# RF.net
KiCad netlist of a schematic drawn in Altium Designer
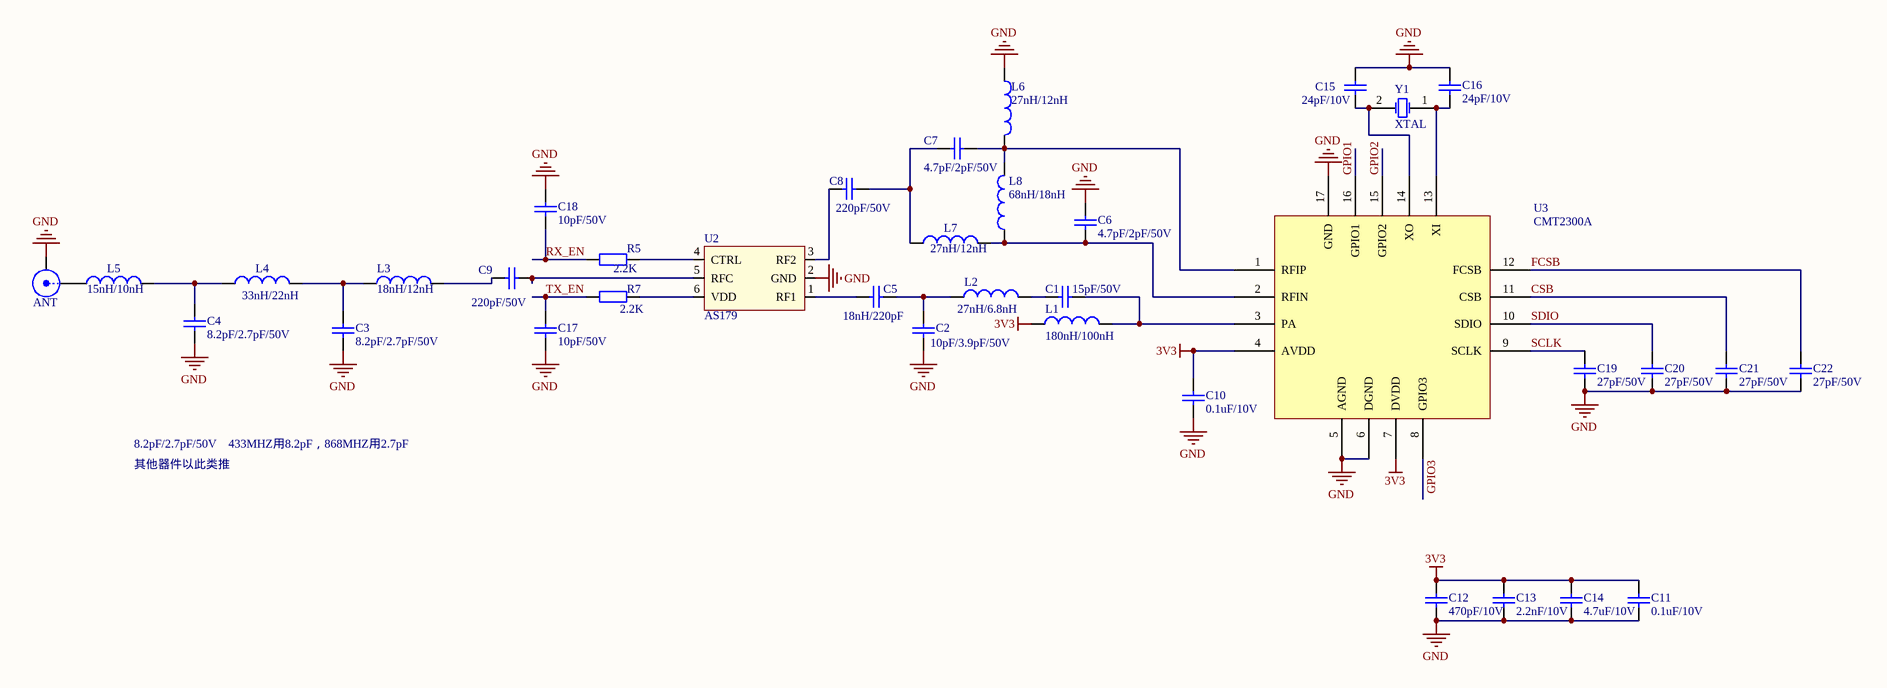
[diagram p0: RF.SchDoc]

(export (version "E")
  (design (tool "Eeschema 10.0.6"))
  (components
    (comp (ref "ANT")
      (value "~")
      (footprint "SMA Straight SMD")
      (description "SMA Straight Connector")
      (fields (field (name "PUBLISHER") "Altium Limited"))
      (libsource (lib "SX1276_e266v02a") (part "SMA"))
    )
    (comp (ref "C1")
      (value "15pF/50V")
      (footprint "0603C")
      (description "Capacitor")
      (fields (field (name "PUBLISHER") "Altium Limited"))
      (libsource (lib "Miscellaneous Devices") (part "Cap"))
    )
    (comp (ref "C2")
      (value "10pF/3.9pF/50V")
      (footprint "0603C")
      (description "Capacitor")
      (fields (field (name "PUBLISHER") "Altium Limited"))
      (libsource (lib "Miscellaneous Devices") (part "Cap"))
    )
    (comp (ref "C3")
      (value "8.2pF/2.7pF/50V")
      (footprint "0603C")
      (description "Capacitor")
      (fields (field (name "PUBLISHER") "Altium Limited"))
      (libsource (lib "Miscellaneous Devices") (part "Cap"))
    )
    (comp (ref "C4")
      (value "8.2pF/2.7pF/50V")
      (footprint "0603C")
      (description "Capacitor")
      (fields (field (name "PUBLISHER") "Altium Limited"))
      (libsource (lib "Miscellaneous Devices") (part "Cap"))
    )
    (comp (ref "C5")
      (value "18nH/220pF")
      (footprint "0603C")
      (description "Capacitor")
      (fields (field (name "PUBLISHER") "Altium Limited"))
      (libsource (lib "Miscellaneous Devices") (part "Cap"))
    )
    (comp (ref "C6")
      (value "4.7pF/2pF/50V")
      (footprint "0603C")
      (description "Capacitor")
      (fields (field (name "PUBLISHER") "Altium Limited"))
      (libsource (lib "Miscellaneous Devices") (part "Cap"))
    )
    (comp (ref "C7")
      (value "4.7pF/2pF/50V")
      (footprint "0603C")
      (description "Capacitor")
      (fields (field (name "PUBLISHER") "Altium Limited"))
      (libsource (lib "Miscellaneous Devices") (part "Cap"))
    )
    (comp (ref "C8")
      (value "220pF/50V")
      (footprint "0603C")
      (description "Capacitor")
      (fields (field (name "PUBLISHER") "Altium Limited"))
      (libsource (lib "Miscellaneous Devices") (part "Cap"))
    )
    (comp (ref "C9")
      (value "220pF/50V")
      (footprint "0603C")
      (description "Capacitor")
      (fields (field (name "PUBLISHER") "Altium Limited"))
      (libsource (lib "Miscellaneous Devices") (part "Cap"))
    )
    (comp (ref "C10")
      (value "0.1uF/10V")
      (footprint "0603C")
      (description "Capacitor")
      (fields (field (name "PUBLISHER") "Altium Limited"))
      (libsource (lib "Miscellaneous Devices") (part "Cap"))
    )
    (comp (ref "C11")
      (value "0.1uF/10V")
      (footprint "0603C")
      (description "Capacitor")
      (fields (field (name "PUBLISHER") "Altium Limited"))
      (libsource (lib "Miscellaneous Devices") (part "Cap"))
    )
    (comp (ref "C12")
      (value "470pF/10V")
      (footprint "0603C")
      (description "Capacitor")
      (fields (field (name "PUBLISHER") "Altium Limited"))
      (libsource (lib "Miscellaneous Devices") (part "Cap"))
    )
    (comp (ref "C13")
      (value "2.2nF/10V")
      (footprint "0603C")
      (description "Capacitor")
      (fields (field (name "PUBLISHER") "Altium Limited"))
      (libsource (lib "Miscellaneous Devices") (part "Cap"))
    )
    (comp (ref "C14")
      (value "4.7uF/10V")
      (footprint "0603C")
      (description "Capacitor")
      (fields (field (name "PUBLISHER") "Altium Limited"))
      (libsource (lib "Miscellaneous Devices") (part "Cap"))
    )
    (comp (ref "C15")
      (value "24pF/10V")
      (footprint "0603C")
      (description "Capacitor")
      (fields (field (name "PUBLISHER") "Altium Limited"))
      (libsource (lib "Miscellaneous Devices") (part "Cap"))
    )
    (comp (ref "C16")
      (value "24pF/10V")
      (footprint "0603C")
      (description "Capacitor")
      (fields (field (name "PUBLISHER") "Altium Limited"))
      (libsource (lib "Miscellaneous Devices") (part "Cap"))
    )
    (comp (ref "C17")
      (value "10pF/50V")
      (footprint "0603C")
      (description "Capacitor")
      (fields (field (name "PUBLISHER") "Altium Limited"))
      (libsource (lib "Miscellaneous Devices") (part "Cap"))
    )
    (comp (ref "C18")
      (value "10pF/50V")
      (footprint "0603C")
      (description "Capacitor")
      (fields (field (name "PUBLISHER") "Altium Limited"))
      (libsource (lib "Miscellaneous Devices") (part "Cap"))
    )
    (comp (ref "C19")
      (value "27pF/50V")
      (footprint "0603C")
      (description "Capacitor")
      (fields (field (name "PUBLISHER") "Altium Limited"))
      (libsource (lib "Miscellaneous Devices") (part "Cap"))
    )
    (comp (ref "C20")
      (value "27pF/50V")
      (footprint "0603C")
      (description "Capacitor")
      (fields (field (name "PUBLISHER") "Altium Limited"))
      (libsource (lib "Miscellaneous Devices") (part "Cap"))
    )
    (comp (ref "C21")
      (value "27pF/50V")
      (footprint "0603C")
      (description "Capacitor")
      (fields (field (name "PUBLISHER") "Altium Limited"))
      (libsource (lib "Miscellaneous Devices") (part "Cap"))
    )
    (comp (ref "C22")
      (value "27pF/50V")
      (footprint "0603C")
      (description "Capacitor")
      (fields (field (name "PUBLISHER") "Altium Limited"))
      (libsource (lib "Miscellaneous Devices") (part "Cap"))
    )
    (comp (ref "L1")
      (value "180nH/100nH")
      (footprint "0603R")
      (description "Inductor")
      (fields (field (name "PUBLISHER") "Altium Limited"))
      (libsource (lib "Miscellaneous Devices") (part "Inductor"))
    )
    (comp (ref "L2")
      (value "27nH/6.8nH")
      (footprint "0603R")
      (description "Inductor")
      (fields (field (name "PUBLISHER") "Altium Limited"))
      (libsource (lib "Miscellaneous Devices") (part "Inductor"))
    )
    (comp (ref "L3")
      (value "18nH/12nH")
      (footprint "0603R")
      (description "Inductor")
      (fields (field (name "PUBLISHER") "Altium Limited"))
      (libsource (lib "Miscellaneous Devices") (part "Inductor"))
    )
    (comp (ref "L4")
      (value "33nH/22nH")
      (footprint "0603R")
      (description "Inductor")
      (fields (field (name "PUBLISHER") "Altium Limited"))
      (libsource (lib "Miscellaneous Devices") (part "Inductor"))
    )
    (comp (ref "L5")
      (value "15nH/10nH")
      (footprint "0603R")
      (description "Inductor")
      (fields (field (name "PUBLISHER") "Altium Limited"))
      (libsource (lib "Miscellaneous Devices") (part "Inductor"))
    )
    (comp (ref "L6")
      (value "27nH/12nH")
      (footprint "0603R")
      (description "Inductor")
      (fields (field (name "PUBLISHER") "Altium Limited"))
      (libsource (lib "Miscellaneous Devices") (part "Inductor"))
    )
    (comp (ref "L7")
      (value "27nH/12nH")
      (footprint "0603R")
      (description "Inductor")
      (fields (field (name "PUBLISHER") "Altium Limited"))
      (libsource (lib "Miscellaneous Devices") (part "Inductor"))
    )
    (comp (ref "L8")
      (value "68nH/18nH")
      (footprint "0603R")
      (description "Inductor")
      (fields (field (name "PUBLISHER") "Altium Limited"))
      (libsource (lib "Miscellaneous Devices") (part "Inductor"))
    )
    (comp (ref "R5")
      (value "2.2K")
      (footprint "0603R")
      (description "Resistor")
      (fields (field (name "PUBLISHER") "Altium Limited"))
      (libsource (lib "Miscellaneous Devices") (part "Res2"))
    )
    (comp (ref "R7")
      (value "2.2K")
      (footprint "0603R")
      (description "Resistor")
      (fields (field (name "PUBLISHER") "Altium Limited"))
      (libsource (lib "Miscellaneous Devices") (part "Res2"))
    )
    (comp (ref "U2")
      (value "AS179")
      (description "PE4259 Peregrine RF Switch")
      (libsource (lib "SX1276_e266v02a") (part "PE4259 RF Switch"))
    )
    (comp (ref "U3") (value "CMT2300A") (libsource (lib "Schlib_20110825") (part "CMT2300A")))
    (comp (ref "Y1")
      (value "XTAL")
      (footprint "BCY-W2/D3.1")
      (description "Crystal Oscillator")
      (fields (field (name "PUBLISHER") "Altium Limited"))
      (libsource (lib "Miscellaneous Devices") (part "XTAL"))
    )
  )
  (nets
    (net (code "1") (name "/CSB") (class "Default")
      (node (ref "C21") (pin "1") (pinfunction "1_1") (pintype "passive"))
      (node (ref "U3") (pin "11") (pinfunction "CSB_11") (pintype "passive"))
    )
    (net (code "2") (name "/FCSB") (class "Default")
      (node (ref "C22") (pin "1") (pinfunction "1_1") (pintype "passive"))
      (node (ref "U3") (pin "12") (pinfunction "FCSB_12") (pintype "passive"))
    )
    (net (code "3") (name "/GPIO1") (class "Default")
      (node (ref "U3") (pin "16") (pinfunction "GPIO1_16") (pintype "passive"))
    )
    (net (code "4") (name "/GPIO2") (class "Default")
      (node (ref "U3") (pin "15") (pinfunction "GPIO2_15") (pintype "passive"))
    )
    (net (code "5") (name "/GPIO3") (class "Default")
      (node (ref "U3") (pin "8") (pinfunction "GPIO3_8") (pintype "passive"))
    )
    (net (code "6") (name "/RX_EN") (class "Default")
      (node (ref "C18") (pin "1") (pinfunction "1_1") (pintype "passive"))
      (node (ref "R5") (pin "2") (pinfunction "2_2") (pintype "passive"))
    )
    (net (code "7") (name "/SCLK") (class "Default")
      (node (ref "C19") (pin "1") (pinfunction "1_1") (pintype "passive"))
      (node (ref "U3") (pin "9") (pinfunction "SCLK_9") (pintype "passive"))
    )
    (net (code "8") (name "/SDIO") (class "Default")
      (node (ref "C20") (pin "1") (pinfunction "1_1") (pintype "passive"))
      (node (ref "U3") (pin "10") (pinfunction "SDIO_10") (pintype "passive"))
    )
    (net (code "9") (name "/TX_EN") (class "Default")
      (node (ref "C17") (pin "2") (pinfunction "2_2") (pintype "passive"))
      (node (ref "R7") (pin "2") (pinfunction "2_2") (pintype "passive"))
    )
    (net (code "10") (name "3V3") (class "Default")
      (node (ref "C10") (pin "1") (pinfunction "1_1") (pintype "passive"))
      (node (ref "C11") (pin "1") (pinfunction "1_1") (pintype "passive"))
      (node (ref "C12") (pin "1") (pinfunction "1_1") (pintype "passive"))
      (node (ref "C13") (pin "1") (pinfunction "1_1") (pintype "passive"))
      (node (ref "C14") (pin "1") (pinfunction "1_1") (pintype "passive"))
      (node (ref "L1") (pin "1") (pinfunction "1_1") (pintype "passive"))
      (node (ref "U3") (pin "4") (pinfunction "AVDD_4") (pintype "passive"))
      (node (ref "U3") (pin "7") (pinfunction "DVDD_7") (pintype "passive"))
    )
    (net (code "11") (name "GND") (class "Default")
      (node (ref "ANT") (pin "2") (pinfunction "GND_2") (pintype "passive"))
      (node (ref "C10") (pin "2") (pinfunction "2_2") (pintype "passive"))
      (node (ref "C11") (pin "2") (pinfunction "2_2") (pintype "passive"))
      (node (ref "C12") (pin "2") (pinfunction "2_2") (pintype "passive"))
      (node (ref "C13") (pin "2") (pinfunction "2_2") (pintype "passive"))
      (node (ref "C14") (pin "2") (pinfunction "2_2") (pintype "passive"))
      (node (ref "C15") (pin "1") (pinfunction "1_1") (pintype "passive"))
      (node (ref "C16") (pin "1") (pinfunction "1_1") (pintype "passive"))
      (node (ref "C17") (pin "1") (pinfunction "1_1") (pintype "passive"))
      (node (ref "C18") (pin "2") (pinfunction "2_2") (pintype "passive"))
      (node (ref "C19") (pin "2") (pinfunction "2_2") (pintype "passive"))
      (node (ref "C2") (pin "1") (pinfunction "1_1") (pintype "passive"))
      (node (ref "C20") (pin "2") (pinfunction "2_2") (pintype "passive"))
      (node (ref "C21") (pin "2") (pinfunction "2_2") (pintype "passive"))
      (node (ref "C22") (pin "2") (pinfunction "2_2") (pintype "passive"))
      (node (ref "C3") (pin "2") (pinfunction "2_2") (pintype "passive"))
      (node (ref "C4") (pin "2") (pinfunction "2_2") (pintype "passive"))
      (node (ref "C6") (pin "2") (pinfunction "2_2") (pintype "passive"))
      (node (ref "L6") (pin "1") (pinfunction "1_1") (pintype "passive"))
      (node (ref "U2") (pin "2") (pinfunction "GND_2") (pintype "passive"))
      (node (ref "U3") (pin "17") (pinfunction "GND_17") (pintype "passive"))
      (node (ref "U3") (pin "5") (pinfunction "AGND_5") (pintype "passive"))
      (node (ref "U3") (pin "6") (pinfunction "DGND_6") (pintype "passive"))
    )
    (net (code "12") (name "Net-(ANT-Signal)") (class "Default")
      (node (ref "ANT") (pin "1") (pinfunction "Signal_1") (pintype "passive"))
      (node (ref "L5") (pin "1") (pinfunction "1_1") (pintype "passive"))
    )
    (net (code "13") (name "Net-(C1-Pad1)") (class "Default")
      (node (ref "C1") (pin "1") (pinfunction "1_1") (pintype "passive"))
      (node (ref "L2") (pin "2") (pinfunction "2_2") (pintype "passive"))
    )
    (net (code "14") (name "Net-(C2-Pad2)") (class "Default")
      (node (ref "C2") (pin "2") (pinfunction "2_2") (pintype "passive"))
      (node (ref "C5") (pin "2") (pinfunction "2_2") (pintype "passive"))
      (node (ref "L2") (pin "1") (pinfunction "1_1") (pintype "passive"))
    )
    (net (code "15") (name "Net-(C3-Pad1)") (class "Default")
      (node (ref "C3") (pin "1") (pinfunction "1_1") (pintype "passive"))
      (node (ref "L3") (pin "1") (pinfunction "1_1") (pintype "passive"))
      (node (ref "L4") (pin "2") (pinfunction "2_2") (pintype "passive"))
    )
    (net (code "16") (name "Net-(C4-Pad1)") (class "Default")
      (node (ref "C4") (pin "1") (pinfunction "1_1") (pintype "passive"))
      (node (ref "L4") (pin "1") (pinfunction "1_1") (pintype "passive"))
      (node (ref "L5") (pin "2") (pinfunction "2_2") (pintype "passive"))
    )
    (net (code "17") (name "Net-(C7-Pad1)") (class "Default")
      (node (ref "C7") (pin "1") (pinfunction "1_1") (pintype "passive"))
      (node (ref "C8") (pin "2") (pinfunction "2_2") (pintype "passive"))
      (node (ref "L7") (pin "1") (pinfunction "1_1") (pintype "passive"))
    )
    (net (code "18") (name "Net-(C9-Pad2)") (class "Default")
      (node (ref "C9") (pin "2") (pinfunction "2_2") (pintype "passive"))
      (node (ref "L3") (pin "2") (pinfunction "2_2") (pintype "passive"))
    )
    (net (code "19") (name "Net-(U2-CTRL)") (class "Default")
      (node (ref "R5") (pin "1") (pinfunction "1_1") (pintype "passive"))
      (node (ref "U2") (pin "4") (pinfunction "CTRL_4") (pintype "passive"))
    )
    (net (code "20") (name "Net-(U2-RF1)") (class "Default")
      (node (ref "C5") (pin "1") (pinfunction "1_1") (pintype "passive"))
      (node (ref "U2") (pin "1") (pinfunction "RF1_1") (pintype "passive"))
    )
    (net (code "21") (name "Net-(U2-RF2)") (class "Default")
      (node (ref "C8") (pin "1") (pinfunction "1_1") (pintype "passive"))
      (node (ref "U2") (pin "3") (pinfunction "RF2_3") (pintype "passive"))
    )
    (net (code "22") (name "Net-(U2-RFC)") (class "Default")
      (node (ref "C9") (pin "1") (pinfunction "1_1") (pintype "passive"))
      (node (ref "U2") (pin "5") (pinfunction "RFC_5") (pintype "passive"))
    )
    (net (code "23") (name "Net-(U2-VDD)") (class "Default")
      (node (ref "R7") (pin "1") (pinfunction "1_1") (pintype "passive"))
      (node (ref "U2") (pin "6") (pinfunction "VDD_6") (pintype "passive"))
    )
    (net (code "24") (name "Net-(U3-PA)") (class "Default")
      (node (ref "C1") (pin "2") (pinfunction "2_2") (pintype "passive"))
      (node (ref "L1") (pin "2") (pinfunction "2_2") (pintype "passive"))
      (node (ref "U3") (pin "3") (pinfunction "PA_3") (pintype "passive"))
    )
    (net (code "25") (name "Net-(U3-RFIN)") (class "Default")
      (node (ref "C6") (pin "1") (pinfunction "1_1") (pintype "passive"))
      (node (ref "L7") (pin "2") (pinfunction "2_2") (pintype "passive"))
      (node (ref "L8") (pin "1") (pinfunction "1_1") (pintype "passive"))
      (node (ref "U3") (pin "2") (pinfunction "RFIN_2") (pintype "passive"))
    )
    (net (code "26") (name "Net-(U3-RFIP)") (class "Default")
      (node (ref "C7") (pin "2") (pinfunction "2_2") (pintype "passive"))
      (node (ref "L6") (pin "2") (pinfunction "2_2") (pintype "passive"))
      (node (ref "L8") (pin "2") (pinfunction "2_2") (pintype "passive"))
      (node (ref "U3") (pin "1") (pinfunction "RFIP_1") (pintype "passive"))
    )
    (net (code "27") (name "Net-(U3-XI)") (class "Default")
      (node (ref "C16") (pin "2") (pinfunction "2_2") (pintype "passive"))
      (node (ref "U3") (pin "13") (pinfunction "XI_13") (pintype "passive"))
      (node (ref "Y1") (pin "1") (pinfunction "OSC1_1") (pintype "passive"))
    )
    (net (code "28") (name "Net-(U3-XO)") (class "Default")
      (node (ref "C15") (pin "2") (pinfunction "2_2") (pintype "passive"))
      (node (ref "U3") (pin "14") (pinfunction "XO_14") (pintype "passive"))
      (node (ref "Y1") (pin "2") (pinfunction "OSC2_2") (pintype "passive"))
    )
  )
)
